# 3V_Regulation.net
KiCad netlist of a schematic drawn in Altium Designer
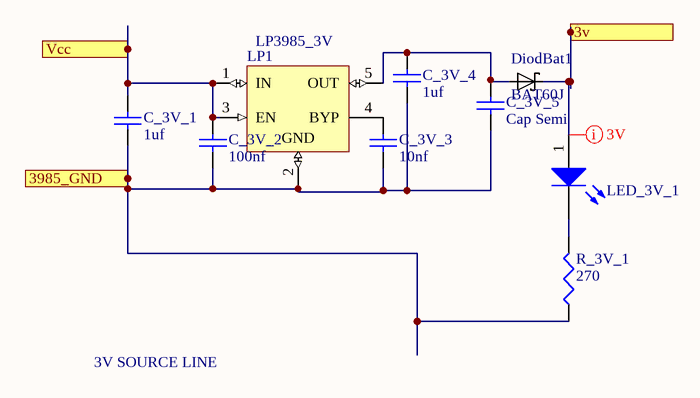
[diagram p0: 3V_Regulation.SchDoc]

(export (version "E")
  (design (tool "Eeschema 10.0.6"))
  (components
    (comp (ref "C_3V_1")
      (value "1uf")
      (footprint "1608(0603)")
      (description "Capacitor (Semiconductor SIM Model)")
      (fields (field (name "PUBLISHER") "Altium Limited"))
      (libsource (lib "Miscellaneous Devices") (part "Cap Semi"))
    )
    (comp (ref "C_3V_2")
      (value "100nf")
      (footprint "1608(0603)")
      (description "Capacitor (Semiconductor SIM Model)")
      (fields (field (name "PUBLISHER") "Altium Limited"))
      (libsource (lib "Miscellaneous Devices") (part "Cap Semi"))
    )
    (comp (ref "C_3V_3")
      (value "10nf")
      (footprint "1608(0603)")
      (description "Capacitor (Semiconductor SIM Model)")
      (fields (field (name "PUBLISHER") "Altium Limited"))
      (libsource (lib "Miscellaneous Devices") (part "Cap Semi"))
    )
    (comp (ref "C_3V_4")
      (value "1uf")
      (footprint "1608(0603)")
      (description "Capacitor (Semiconductor SIM Model)")
      (fields (field (name "PUBLISHER") "Altium Limited"))
      (libsource (lib "Miscellaneous Devices") (part "Cap Semi"))
    )
    (comp (ref "C_3V_5")
      (value "Cap Semi")
      (footprint "1608(0603)")
      (description "Capacitor (Semiconductor SIM Model)")
      (fields (field (name "PUBLISHER") "Altium Limited"))
      (libsource (lib "Miscellaneous Devices") (part "Cap Semi"))
    )
    (comp (ref "DiodBat1")
      (value "BAT60J")
      (footprint "*SOD323_ST_BAT60J(Primary)")
      (fields (field (name "MF") "STMicroelectronics"))
      (libsource (lib "BAT60J") (part "BAT60J"))
    )
    (comp (ref "LED_3V_1")
      (value "L_green")
      (footprint "LED_0603")
      (libsource (lib "Led_edited") (part "L_green"))
    )
    (comp (ref "LP1")
      (value "LP3985_3V")
      (footprint "*SOT95P280X145-5N")
      (description "Micropower, 150mA Low-Noise Ultra Low-Dropout CMOS Voltage Regulator, 5-pin SOT-23")
      (fields
        (field (name "MANUFACTURER") "National Semiconductor")
        (field (name "PARTNUMBER") "LP3985IM5-2.9")
      )
      (libsource (lib "TI_National_Semiconductor_LP3985IM5_2_9") (part "LP3985IM5-2.9"))
    )
    (comp (ref "R_3V_1")
      (value "270")
      (footprint "1608(0603)")
      (description "Resistor")
      (fields (field (name "Comment") "Res3") (field (name "PUBLISHER") "Altium Limited"))
      (libsource (lib "Miscellaneous Devices") (part "Res3"))
    )
  )
  (nets
    (net (code "1") (name "/3v") (class "Default")
      (node (ref "DiodBat1") (pin "C") (pinfunction "C_C") (pintype "passive"))
      (node (ref "LED_3V_1") (pin "1") (pinfunction "V_1") (pintype "passive"))
    )
    (net (code "2") (name "/3985_GND") (class "Default")
      (node (ref "C_3V_1") (pin "1") (pinfunction "1_1") (pintype "passive"))
      (node (ref "C_3V_2") (pin "1") (pinfunction "1_1") (pintype "passive"))
      (node (ref "C_3V_3") (pin "1") (pinfunction "1_1") (pintype "passive"))
      (node (ref "C_3V_4") (pin "1") (pinfunction "1_1") (pintype "passive"))
      (node (ref "C_3V_5") (pin "1") (pinfunction "1_1") (pintype "passive"))
      (node (ref "LP1") (pin "2") (pinfunction "GND_2") (pintype "bidirectional"))
      (node (ref "R_3V_1") (pin "1") (pinfunction "1_1") (pintype "passive"))
    )
    (net (code "3") (name "/Vcc") (class "Default")
      (node (ref "C_3V_1") (pin "2") (pinfunction "2_2") (pintype "passive"))
      (node (ref "C_3V_2") (pin "2") (pinfunction "2_2") (pintype "passive"))
      (node (ref "LP1") (pin "1") (pinfunction "IN_1") (pintype "bidirectional"))
      (node (ref "LP1") (pin "3") (pinfunction "EN_3") (pintype "input"))
    )
    (net (code "4") (name "Net-(LED_3V_1-K)") (class "Default")
      (node (ref "LED_3V_1") (pin "2") (pinfunction "K_2") (pintype "passive"))
      (node (ref "R_3V_1") (pin "2") (pinfunction "2_2") (pintype "passive"))
    )
    (net (code "5") (name "Net-(LP1-BYP)") (class "Default")
      (node (ref "C_3V_3") (pin "2") (pinfunction "2_2") (pintype "passive"))
      (node (ref "LP1") (pin "4") (pinfunction "BYP_4") (pintype "passive"))
    )
    (net (code "6") (name "Net-(LP1-OUT)") (class "Default")
      (node (ref "C_3V_4") (pin "2") (pinfunction "2_2") (pintype "passive"))
      (node (ref "C_3V_5") (pin "2") (pinfunction "2_2") (pintype "passive"))
      (node (ref "DiodBat1") (pin "A") (pinfunction "A_A") (pintype "passive"))
      (node (ref "LP1") (pin "5") (pinfunction "OUT_5") (pintype "bidirectional"))
    )
  )
)
